# PMOD_LEVELSHIFT.net
KiCad netlist of a schematic drawn in Altium Designer
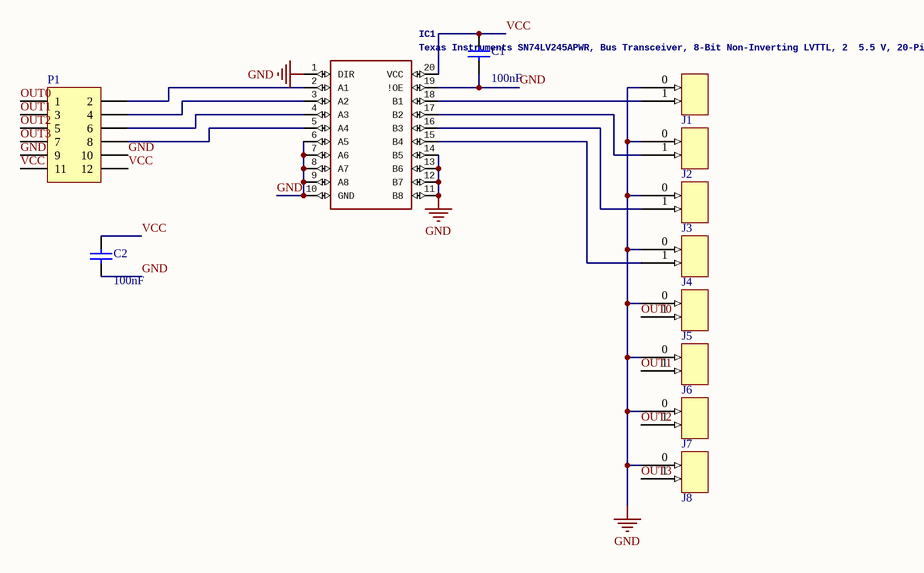
[diagram p0: PMOD_LEVELSHIFT.SchDoc]

(export (version "E")
  (design (tool "Eeschema 10.0.6"))
  (components
    (comp (ref "C1")
      (value "100nF")
      (footprint "RC0805JR-07390RL:*RESC2012X60N")
      (description "Capacitor (Semiconductor SIM Model)")
      (fields (field (name "PUBLISHER") "Altium Limited"))
      (libsource (lib "Miscellaneous Devices") (part "Cap Semi"))
    )
    (comp (ref "C2")
      (value "100nF")
      (footprint "RC0805JR-07390RL:*RESC2012X60N")
      (description "Capacitor (Semiconductor SIM Model)")
      (fields (field (name "PUBLISHER") "Altium Limited"))
      (libsource (lib "Miscellaneous Devices") (part "Cap Semi"))
    )
    (comp (ref "IC1")
      (value "Texas Instruments SN74LV245APWR, Bus Transceiver, 8-Bit Non-Inverting LVTTL, 2  5.5 V, 20-Pin TSSOP   Source:  Datasheet")
      (footprint "SOP65P640X120-20N")
      (fields
        (field (name "RS_PART_NUMBER") "6628483P")
        (field (name "MANUFACTURER_PART_NUMBER") "SN74LV245APWR")
      )
      (libsource (lib "SN74LV245APWR") (part "SN74LV245APWR"))
    )
    (comp (ref "J1") (value "BNC_CON") (footprint "BNC_CON") (libsource (lib "BNC") (part "BNC_CON")))
    (comp (ref "J2") (value "BNC_CON") (footprint "BNC_CON") (libsource (lib "BNC") (part "BNC_CON")))
    (comp (ref "J3") (value "BNC_CON") (footprint "BNC_CON") (libsource (lib "BNC") (part "BNC_CON")))
    (comp (ref "J4") (value "BNC_CON") (footprint "BNC_CON") (libsource (lib "BNC") (part "BNC_CON")))
    (comp (ref "J5") (value "BNC_CON") (footprint "BNC_CON") (libsource (lib "BNC") (part "BNC_CON")))
    (comp (ref "J6") (value "BNC_CON") (footprint "BNC_CON") (libsource (lib "BNC") (part "BNC_CON")))
    (comp (ref "J7") (value "BNC_CON") (footprint "BNC_CON") (libsource (lib "BNC") (part "BNC_CON")))
    (comp (ref "J8") (value "BNC_CON") (footprint "BNC_CON") (libsource (lib "BNC") (part "BNC_CON")))
    (comp (ref "P1")
      (value "~")
      (footprint "TSW-106-08-L-D-RA:HDRRA12W64P254_2X6_1524X254X61")
      (description "Header, 6-Pin, Dual row, Right Angle")
      (fields (field (name "PUBLISHER") "Altium Limited"))
      (libsource (lib "Miscellaneous Connectors") (part "Header 6X2H"))
    )
  )
  (nets
    (net (code "1") (name "/OUT0") (class "Default")
      (node (ref "J5") (pin "1") (pintype "input"))
      (node (ref "P1") (pin "1") (pinfunction "1_1") (pintype "passive"))
    )
    (net (code "2") (name "/OUT1") (class "Default")
      (node (ref "J6") (pin "1") (pintype "input"))
      (node (ref "P1") (pin "3") (pinfunction "3_3") (pintype "passive"))
    )
    (net (code "3") (name "/OUT2") (class "Default")
      (node (ref "J7") (pin "1") (pintype "input"))
      (node (ref "P1") (pin "5") (pinfunction "5_5") (pintype "passive"))
    )
    (net (code "4") (name "/OUT3") (class "Default")
      (node (ref "J8") (pin "1") (pintype "input"))
      (node (ref "P1") (pin "7") (pinfunction "7_7") (pintype "passive"))
    )
    (net (code "5") (name "/VCC") (class "Default")
      (node (ref "C1") (pin "2") (pinfunction "2_2") (pintype "passive"))
      (node (ref "C2") (pin "2") (pinfunction "2_2") (pintype "passive"))
      (node (ref "IC1") (pin "20") (pinfunction "VCC_20") (pintype "bidirectional"))
      (node (ref "P1") (pin "11") (pinfunction "11_11") (pintype "passive"))
      (node (ref "P1") (pin "12") (pinfunction "12_12") (pintype "passive"))
    )
    (net (code "6") (name "GND") (class "Default")
      (node (ref "C1") (pin "1") (pinfunction "1_1") (pintype "passive"))
      (node (ref "C2") (pin "1") (pinfunction "1_1") (pintype "passive"))
      (node (ref "IC1") (pin "1") (pinfunction "DIR_1") (pintype "bidirectional"))
      (node (ref "IC1") (pin "10") (pinfunction "GND_10") (pintype "bidirectional"))
      (node (ref "IC1") (pin "11") (pinfunction "B8_11") (pintype "bidirectional"))
      (node (ref "IC1") (pin "12") (pinfunction "B7_12") (pintype "bidirectional"))
      (node (ref "IC1") (pin "13") (pinfunction "B6_13") (pintype "bidirectional"))
      (node (ref "IC1") (pin "14") (pinfunction "B5_14") (pintype "bidirectional"))
      (node (ref "IC1") (pin "19") (pinfunction "!OE_19") (pintype "bidirectional"))
      (node (ref "IC1") (pin "6") (pinfunction "A5_6") (pintype "bidirectional"))
      (node (ref "IC1") (pin "7") (pinfunction "A6_7") (pintype "bidirectional"))
      (node (ref "IC1") (pin "8") (pinfunction "A7_8") (pintype "bidirectional"))
      (node (ref "IC1") (pin "9") (pinfunction "A8_9") (pintype "bidirectional"))
      (node (ref "J1") (pin "0") (pintype "input"))
      (node (ref "J2") (pin "0") (pintype "input"))
      (node (ref "J3") (pin "0") (pintype "input"))
      (node (ref "J4") (pin "0") (pintype "input"))
      (node (ref "J5") (pin "0") (pintype "input"))
      (node (ref "J6") (pin "0") (pintype "input"))
      (node (ref "J7") (pin "0") (pintype "input"))
      (node (ref "J8") (pin "0") (pintype "input"))
      (node (ref "P1") (pin "10") (pinfunction "10_10") (pintype "passive"))
      (node (ref "P1") (pin "9") (pinfunction "9_9") (pintype "passive"))
    )
    (net (code "7") (name "Net-(IC1-A1)") (class "Default")
      (node (ref "IC1") (pin "2") (pinfunction "A1_2") (pintype "bidirectional"))
      (node (ref "P1") (pin "2") (pinfunction "2_2") (pintype "passive"))
    )
    (net (code "8") (name "Net-(IC1-A2)") (class "Default")
      (node (ref "IC1") (pin "3") (pinfunction "A2_3") (pintype "bidirectional"))
      (node (ref "P1") (pin "4") (pinfunction "4_4") (pintype "passive"))
    )
    (net (code "9") (name "Net-(IC1-A3)") (class "Default")
      (node (ref "IC1") (pin "4") (pinfunction "A3_4") (pintype "bidirectional"))
      (node (ref "P1") (pin "6") (pinfunction "6_6") (pintype "passive"))
    )
    (net (code "10") (name "Net-(IC1-A4)") (class "Default")
      (node (ref "IC1") (pin "5") (pinfunction "A4_5") (pintype "bidirectional"))
      (node (ref "P1") (pin "8") (pinfunction "8_8") (pintype "passive"))
    )
    (net (code "11") (name "Net-(IC1-B1)") (class "Default")
      (node (ref "IC1") (pin "18") (pinfunction "B1_18") (pintype "bidirectional"))
      (node (ref "J1") (pin "1") (pintype "input"))
    )
    (net (code "12") (name "Net-(IC1-B2)") (class "Default")
      (node (ref "IC1") (pin "17") (pinfunction "B2_17") (pintype "bidirectional"))
      (node (ref "J2") (pin "1") (pintype "input"))
    )
    (net (code "13") (name "Net-(IC1-B3)") (class "Default")
      (node (ref "IC1") (pin "16") (pinfunction "B3_16") (pintype "bidirectional"))
      (node (ref "J3") (pin "1") (pintype "input"))
    )
    (net (code "14") (name "Net-(IC1-B4)") (class "Default")
      (node (ref "IC1") (pin "15") (pinfunction "B4_15") (pintype "bidirectional"))
      (node (ref "J4") (pin "1") (pintype "input"))
    )
  )
)
